# micro-sd-card-reader.net
KiCad netlist of a schematic drawn in Altium Designer
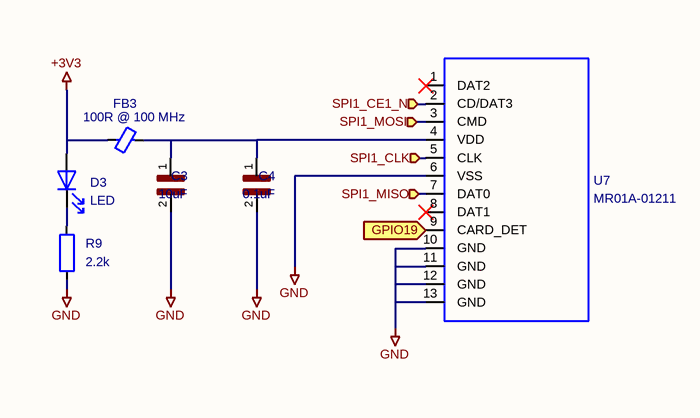
[diagram p0: micro-sd-card-reader.SchDoc]

(export (version "E")
  (design (tool "Eeschema 10.0.6"))
  (components
    (comp (ref "C3") (value "10uF") (libsource (lib "Daughterboard_Symbols") (part "CL10B104KB8NNNL")))
    (comp (ref "C4") (value "0.1uF") (libsource (lib "Daughterboard_Symbols") (part "CL10B104KB8NNNL")))
    (comp (ref "D3") (value "LED") (libsource (lib "Device") (part "LED")))
    (comp (ref "FB3") (value "100R @ 100 MHz") (libsource (lib "Device") (part "FerriteBead_Small")))
    (comp (ref "R9") (value "2.2k") (libsource (lib "Device") (part "R")))
    (comp (ref "U7") (value "MR01A-01211") (libsource (lib "Imported_OBC_Library") (part "MR01A-01211")))
  )
  (nets
    (net (code "1") (name "+3V3") (class "Default")
      (node (ref "D3") (pin "2") (pinfunction "A_2") (pintype "passive"))
      (node (ref "FB3") (pin "1") (pinfunction "1_1") (pintype "passive"))
    )
    (net (code "2") (name "/GPIO19") (class "Default")
      (node (ref "U7") (pin "9") (pinfunction "CARD_DET_9") (pintype "passive"))
    )
    (net (code "3") (name "/SPI1_CE1_N") (class "Default")
      (node (ref "U7") (pin "2") (pinfunction "CD/DAT3_2") (pintype "passive"))
    )
    (net (code "4") (name "/SPI1_CLK") (class "Default")
      (node (ref "U7") (pin "5") (pinfunction "CLK_5") (pintype "passive"))
    )
    (net (code "5") (name "/SPI1_MISO") (class "Default")
      (node (ref "U7") (pin "7") (pinfunction "DAT0_7") (pintype "passive"))
    )
    (net (code "6") (name "/SPI1_MOSI") (class "Default")
      (node (ref "U7") (pin "3") (pinfunction "CMD_3") (pintype "passive"))
    )
    (net (code "7") (name "GND") (class "Default")
      (node (ref "C3") (pin "2") (pinfunction "2_2") (pintype "passive"))
      (node (ref "C4") (pin "2") (pinfunction "2_2") (pintype "passive"))
      (node (ref "R9") (pin "2") (pinfunction "2_2") (pintype "passive"))
      (node (ref "U7") (pin "10") (pinfunction "GND_10") (pintype "passive"))
      (node (ref "U7") (pin "11") (pinfunction "GND_11") (pintype "passive"))
      (node (ref "U7") (pin "12") (pinfunction "GND_12") (pintype "passive"))
      (node (ref "U7") (pin "13") (pinfunction "GND_13") (pintype "passive"))
      (node (ref "U7") (pin "6") (pinfunction "VSS_6") (pintype "passive"))
    )
    (net (code "8") (name "Net-(D3-K)") (class "Default")
      (node (ref "D3") (pin "1") (pinfunction "K_1") (pintype "passive"))
      (node (ref "R9") (pin "1") (pinfunction "1_1") (pintype "passive"))
    )
    (net (code "9") (name "Net-(U7-VDD)") (class "Default")
      (node (ref "C3") (pin "1") (pinfunction "1_1") (pintype "passive"))
      (node (ref "C4") (pin "1") (pinfunction "1_1") (pintype "passive"))
      (node (ref "FB3") (pin "2") (pinfunction "2_2") (pintype "passive"))
      (node (ref "U7") (pin "4") (pinfunction "VDD_4") (pintype "passive"))
    )
    (net (code "10") (name "unconnected-(U7-DAT1-Pad8)") (class "Default")
      (node (ref "U7") (pin "8") (pinfunction "DAT1_8") (pintype "passive+no_connect"))
    )
    (net (code "11") (name "unconnected-(U7-DAT2-Pad1)") (class "Default")
      (node (ref "U7") (pin "1") (pinfunction "DAT2_1") (pintype "passive+no_connect"))
    )
  )
)
